# SAMD51.net
KiCad netlist of a schematic drawn in Altium Designer
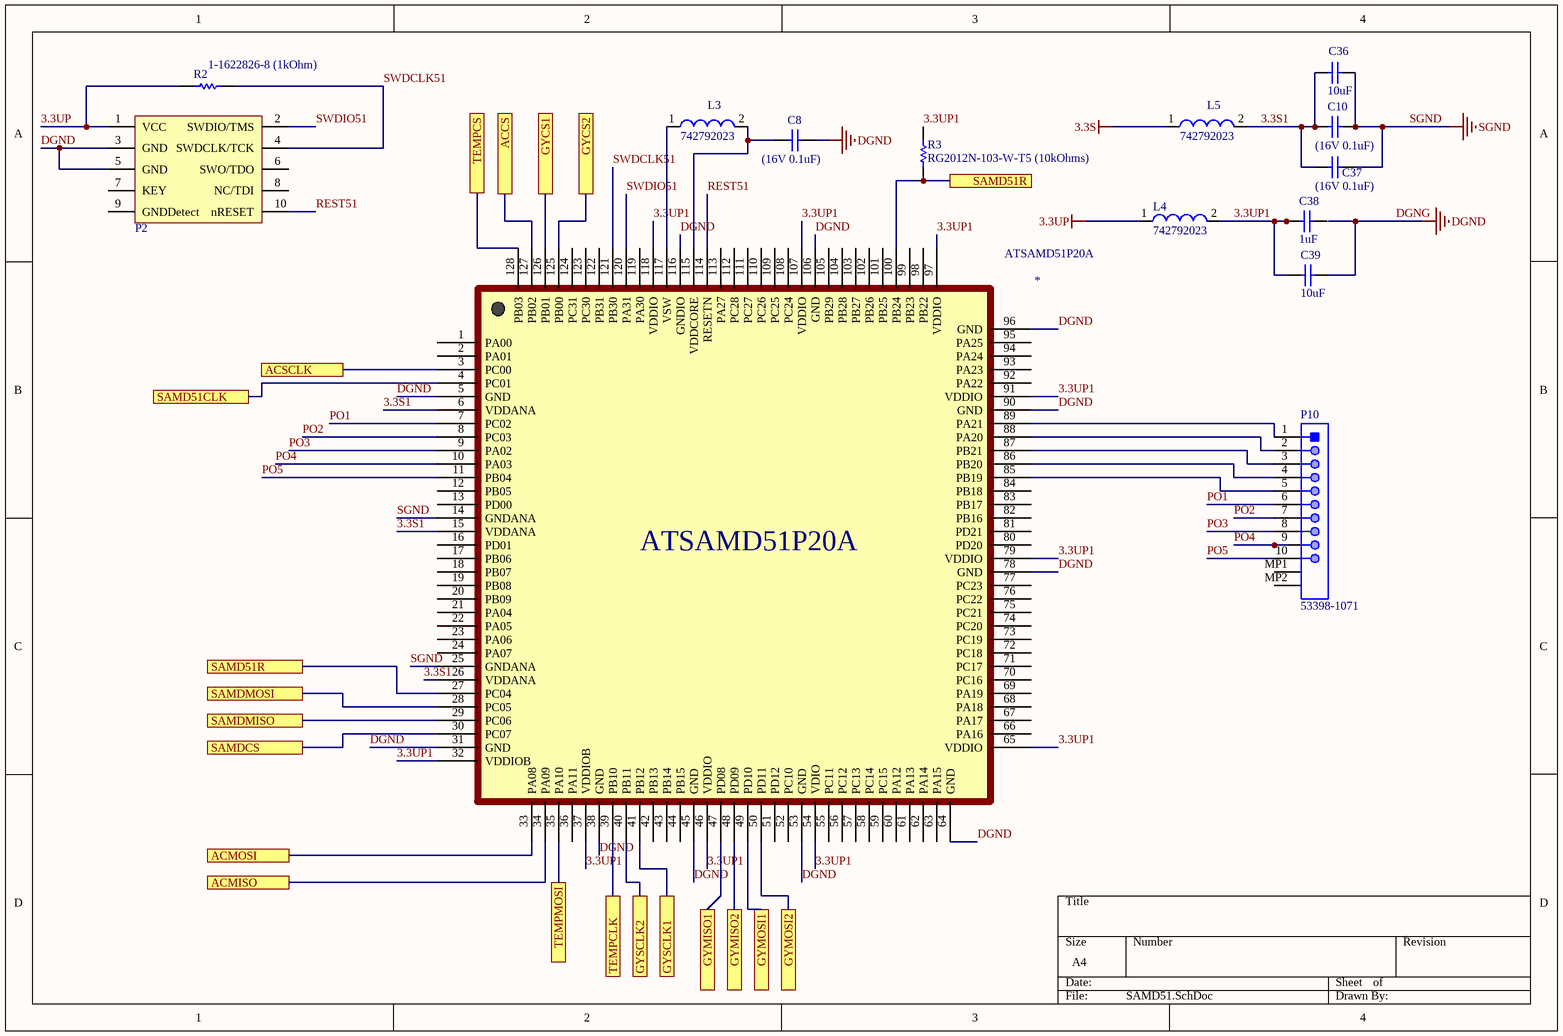
[diagram p0: SAMD51.SchDoc]

(export (version "E")
  (design (tool "Eeschema 10.0.6"))
  (components
    (comp (ref "*")
      (value "ATSAMD51P20A")
      (footprint "ATSAMD51P20A")
      (description "https://www.microchip.com/wwwproducts/en/ATSAMD51P20A#additional-features")
      (libsource (lib "ATSAMD51P20A") (part "ATSAMD51P20A"))
    )
    (comp (ref "C8")
      (value "(16V 0.1uF)")
      (footprint "CAPC1608X90X35LL15T15")
      (fields
        (field (name "PART NUMBER") "0603YC104MAT4A")
        (field (name "MANUFACTURER") "AVX Interconnect / Elco")
      )
      (libsource (lib "Altium Content Vault") (part "CAP"))
    )
    (comp (ref "C10")
      (value "(16V 0.1uF)")
      (footprint "CAPC1608X90X35LL15T15")
      (fields
        (field (name "PART NUMBER") "0603YC104MAT4A")
        (field (name "MANUFACTURER") "AVX Interconnect / Elco")
      )
      (libsource (lib "Altium Content Vault") (part "CAP"))
    )
    (comp (ref "C36")
      (value "10uF")
      (footprint "CAPC1608X90X35NL10T15")
      (fields (field (name "PART NUMBER") "GRM188R60J106ME47D") (field (name "MANUFACTURER") "Murata"))
      (libsource (lib "Altium Content Vault") (part "CAP"))
    )
    (comp (ref "C37")
      (value "(16V 0.1uF)")
      (footprint "CAPC1608X90X35LL15T15")
      (fields
        (field (name "PART NUMBER") "0603YC104MAT4A")
        (field (name "MANUFACTURER") "AVX Interconnect / Elco")
      )
      (libsource (lib "Altium Content Vault") (part "CAP"))
    )
    (comp (ref "C38")
      (value "1uF")
      (footprint "CAPC1608X90X35LL15T15")
      (fields
        (field (name "PART NUMBER") "0603ZC105KAT2A")
        (field (name "MANUFACTURER") "AVX Interconnect / Elco")
      )
      (libsource (lib "Altium Content Vault") (part "CAP"))
    )
    (comp (ref "C39")
      (value "10uF")
      (footprint "CAPC1608X90X35NL10T15")
      (fields (field (name "PART NUMBER") "GRM188R60J106ME47D") (field (name "MANUFACTURER") "Murata"))
      (libsource (lib "Altium Content Vault") (part "CAP"))
    )
    (comp (ref "L3")
      (value "742792023")
      (footprint "SMD-0805")
      (description "SMD EMI Suppression Ferrite Bead WE-CBF, Z = 120 Ohm")
      (libsource (lib "Altium Content Vault") (part "PAS-IND-INDUCTOR-2"))
    )
    (comp (ref "L4")
      (value "742792023")
      (footprint "SMD-0805")
      (description "SMD EMI Suppression Ferrite Bead WE-CBF, Z = 120 Ohm")
      (libsource (lib "Altium Content Vault") (part "PAS-IND-INDUCTOR-2"))
    )
    (comp (ref "L5")
      (value "742792023")
      (footprint "SMD-0805")
      (description "SMD EMI Suppression Ferrite Bead WE-CBF, Z = 120 Ohm")
      (libsource (lib "Altium Content Vault") (part "PAS-IND-INDUCTOR-2"))
    )
    (comp (ref "P2")
      (value "3220-10-0100-00 Pin connector for Cotex Programmers")
      (description "3220-10-0100-00 Pin connector from DigiKey")
      (libsource (lib "3220-10-0100-00") (part "3220-10-0100-00"))
    )
    (comp (ref "P10")
      (value "53398-1071")
      (footprint "MOLX-53398-1071_V")
      (description "Male Header, Pitch 1.25 mm, 1 x 10 Position, Height 4.7 mm, -40 to 85 degC, RoHS, Tape and Reel")
      (fields (field (name "MANUFACTURER") "Molex"))
      (libsource (lib "Altium Content Vault") (part "CN-1P-2M-R10"))
    )
    (comp (ref "R2")
      (value "1-1622826-8 (1kOhm)")
      (footprint "RESC1005X40X25ML10T10")
      (fields
        (field (name "MANUFACTURER") "TE Connectivity / AMP")
        (field (name "PART NUMBER") "1-1622826-8")
      )
      (libsource (lib "Altium Content Vault") (part "RES"))
    )
    (comp (ref "R3")
      (value "RG2012N-103-W-T5 (10kOhms)")
      (footprint "RESC2013X50X40NL20T20")
      (fields (field (name "MANUFACTURER") "Susumu") (field (name "PART NUMBER") "RG2012N-103-W-T5"))
      (libsource (lib "Altium Content Vault") (part "RES"))
    )
  )
  (nets
    (net (code "1") (name "/3.3S1") (class "Default")
      (node (ref "*") (pin "15") (pinfunction "VDDANA_15") (pintype "passive"))
      (node (ref "*") (pin "26") (pinfunction "VDDANA_26") (pintype "passive"))
      (node (ref "*") (pin "6") (pinfunction "VDDANA_6") (pintype "passive"))
      (node (ref "C10") (pin "1") (pinfunction "1_1") (pintype "passive"))
      (node (ref "C36") (pin "2") (pinfunction "2_2") (pintype "passive"))
      (node (ref "C37") (pin "1") (pinfunction "1_1") (pintype "passive"))
      (node (ref "L5") (pin "2") (pinfunction "2_2") (pintype "passive"))
    )
    (net (code "2") (name "/3.3UP1") (class "Default")
      (node (ref "*") (pin "107") (pinfunction "VDDIO_107") (pintype "passive"))
      (node (ref "*") (pin "118") (pinfunction "VDDIO_118") (pintype "passive"))
      (node (ref "*") (pin "32") (pinfunction "VDDIOB_32") (pintype "passive"))
      (node (ref "*") (pin "37") (pinfunction "VDDIOB_37") (pintype "passive"))
      (node (ref "*") (pin "46") (pinfunction "VDDIO_46") (pintype "passive"))
      (node (ref "*") (pin "54") (pinfunction "VDIO_54") (pintype "passive"))
      (node (ref "*") (pin "65") (pinfunction "VDDIO_65") (pintype "passive"))
      (node (ref "*") (pin "79") (pinfunction "VDDIO_79") (pintype "passive"))
      (node (ref "*") (pin "91") (pinfunction "VDDIO_91") (pintype "passive"))
      (node (ref "*") (pin "97") (pinfunction "VDDIO_97") (pintype "passive"))
      (node (ref "C38") (pin "2") (pinfunction "2_2") (pintype "passive"))
      (node (ref "C39") (pin "2") (pinfunction "2_2") (pintype "passive"))
      (node (ref "L4") (pin "2") (pinfunction "2_2") (pintype "passive"))
      (node (ref "R3") (pin "2") (pinfunction "2_2") (pintype "passive"))
    )
    (net (code "3") (name "/ACCS") (class "Default")
      (node (ref "*") (pin "127") (pinfunction "PB02_127") (pintype "passive"))
    )
    (net (code "4") (name "/ACMISO") (class "Default")
      (node (ref "*") (pin "34") (pinfunction "PA09_34") (pintype "passive"))
    )
    (net (code "5") (name "/ACMOSI") (class "Default")
      (node (ref "*") (pin "33") (pinfunction "PA08_33") (pintype "passive"))
    )
    (net (code "6") (name "/ACSCLK") (class "Default")
      (node (ref "*") (pin "3") (pinfunction "PC00_3") (pintype "passive"))
    )
    (net (code "7") (name "/GYCS1") (class "Default")
      (node (ref "*") (pin "126") (pinfunction "PB01_126") (pintype "passive"))
    )
    (net (code "8") (name "/GYCS2") (class "Default")
      (node (ref "*") (pin "125") (pinfunction "PB00_125") (pintype "passive"))
    )
    (net (code "9") (name "/GYMISO1") (class "Default")
      (node (ref "*") (pin "47") (pinfunction "PD08_47") (pintype "passive"))
    )
    (net (code "10") (name "/GYMISO2") (class "Default")
      (node (ref "*") (pin "48") (pinfunction "PD09_48") (pintype "passive"))
    )
    (net (code "11") (name "/GYMOSI1") (class "Default")
      (node (ref "*") (pin "49") (pinfunction "PD10_49") (pintype "passive"))
    )
    (net (code "12") (name "/GYMOSI2") (class "Default")
      (node (ref "*") (pin "50") (pinfunction "PD11_50") (pintype "passive"))
    )
    (net (code "13") (name "/GYSCLK1") (class "Default")
      (node (ref "*") (pin "41") (pinfunction "PB12_41") (pintype "passive"))
    )
    (net (code "14") (name "/GYSCLK2") (class "Default")
      (node (ref "*") (pin "40") (pinfunction "PB11_40") (pintype "passive"))
    )
    (net (code "15") (name "/PO1") (class "Default")
      (node (ref "*") (pin "7") (pinfunction "PC02_7") (pintype "passive"))
      (node (ref "P10") (pin "6") (pinfunction "6_6") (pintype "passive"))
    )
    (net (code "16") (name "/PO2") (class "Default")
      (node (ref "*") (pin "8") (pinfunction "PC03_8") (pintype "passive"))
      (node (ref "P10") (pin "7") (pinfunction "7_7") (pintype "passive"))
    )
    (net (code "17") (name "/PO3") (class "Default")
      (node (ref "*") (pin "9") (pinfunction "PA02_9") (pintype "passive"))
      (node (ref "P10") (pin "8") (pinfunction "8_8") (pintype "passive"))
    )
    (net (code "18") (name "/PO4") (class "Default")
      (node (ref "*") (pin "10") (pinfunction "PA03_10") (pintype "passive"))
      (node (ref "P10") (pin "9") (pinfunction "9_9") (pintype "passive"))
    )
    (net (code "19") (name "/PO5") (class "Default")
      (node (ref "*") (pin "11") (pinfunction "PB04_11") (pintype "passive"))
      (node (ref "P10") (pin "10") (pinfunction "10_10") (pintype "passive"))
    )
    (net (code "20") (name "/REST51") (class "Default")
      (node (ref "*") (pin "114") (pinfunction "RESETN_114") (pintype "passive"))
      (node (ref "P2") (pin "10") (pinfunction "nRESET_10") (pintype "passive"))
    )
    (net (code "21") (name "/SAMD51CLK") (class "Default")
      (node (ref "*") (pin "4") (pinfunction "PC01_4") (pintype "passive"))
    )
    (net (code "22") (name "/SAMD51R") (class "Default")
      (node (ref "*") (pin "100") (pinfunction "PB24_100") (pintype "passive"))
      (node (ref "*") (pin "27") (pinfunction "PC04_27") (pintype "passive"))
      (node (ref "R3") (pin "1") (pinfunction "1_1") (pintype "passive"))
    )
    (net (code "23") (name "/SAMDCS") (class "Default")
      (node (ref "*") (pin "30") (pinfunction "PC07_30") (pintype "passive"))
    )
    (net (code "24") (name "/SAMDMISO") (class "Default")
      (node (ref "*") (pin "29") (pinfunction "PC06_29") (pintype "passive"))
    )
    (net (code "25") (name "/SAMDMOSI") (class "Default")
      (node (ref "*") (pin "28") (pinfunction "PC05_28") (pintype "passive"))
    )
    (net (code "26") (name "/SWDCLK51") (class "Default")
      (node (ref "*") (pin "121") (pinfunction "PB30_121") (pintype "passive"))
      (node (ref "P2") (pin "4") (pinfunction "SWDCLK/TCK_4") (pintype "passive"))
      (node (ref "R2") (pin "1") (pinfunction "1_1") (pintype "passive"))
    )
    (net (code "27") (name "/SWDIO51") (class "Default")
      (node (ref "*") (pin "120") (pinfunction "PA31_120") (pintype "passive"))
      (node (ref "P2") (pin "2") (pinfunction "SWDIO/TMS_2") (pintype "passive"))
    )
    (net (code "28") (name "/TEMPCLK") (class "Default")
      (node (ref "*") (pin "39") (pinfunction "PB10_39") (pintype "passive"))
    )
    (net (code "29") (name "/TEMPCS") (class "Default")
      (node (ref "*") (pin "128") (pinfunction "PB03_128") (pintype "passive"))
    )
    (net (code "30") (name "/TEMPMOSI") (class "Default")
      (node (ref "*") (pin "35") (pinfunction "PA10_35") (pintype "passive"))
    )
    (net (code "31") (name "3.3S") (class "Default")
      (node (ref "L5") (pin "1") (pinfunction "1_1") (pintype "passive"))
    )
    (net (code "32") (name "3.3UP") (class "Default")
      (node (ref "L4") (pin "1") (pinfunction "1_1") (pintype "passive"))
      (node (ref "P2") (pin "1") (pinfunction "VCC_1") (pintype "passive"))
      (node (ref "R2") (pin "2") (pinfunction "2_2") (pintype "passive"))
    )
    (net (code "33") (name "DGND") (class "Default")
      (node (ref "*") (pin "106") (pinfunction "GND_106") (pintype "passive"))
      (node (ref "*") (pin "116") (pinfunction "GNDIO_116") (pintype "passive"))
      (node (ref "*") (pin "31") (pinfunction "GND_31") (pintype "passive"))
      (node (ref "*") (pin "38") (pinfunction "GND_38") (pintype "passive"))
      (node (ref "*") (pin "45") (pinfunction "GND_45") (pintype "passive"))
      (node (ref "*") (pin "5") (pinfunction "GND_5") (pintype "passive"))
      (node (ref "*") (pin "53") (pinfunction "GND_53") (pintype "passive"))
      (node (ref "*") (pin "64") (pinfunction "GND_64") (pintype "passive"))
      (node (ref "*") (pin "78") (pinfunction "GND_78") (pintype "passive"))
      (node (ref "*") (pin "90") (pinfunction "GND_90") (pintype "passive"))
      (node (ref "*") (pin "96") (pinfunction "GND_96") (pintype "passive"))
      (node (ref "C39") (pin "1") (pinfunction "1_1") (pintype "passive"))
      (node (ref "C8") (pin "2") (pinfunction "2_2") (pintype "passive"))
      (node (ref "P2") (pin "3") (pinfunction "GND_3") (pintype "passive"))
      (node (ref "P2") (pin "5") (pinfunction "GND_5") (pintype "passive"))
    )
    (net (code "34") (name "Net-(*-PA20)") (class "Default")
      (node (ref "*") (pin "88") (pinfunction "PA20_88") (pintype "passive"))
      (node (ref "P10") (pin "2") (pinfunction "2_2") (pintype "passive"))
    )
    (net (code "35") (name "Net-(*-PA21)") (class "Default")
      (node (ref "*") (pin "89") (pinfunction "PA21_89") (pintype "passive"))
      (node (ref "P10") (pin "1") (pinfunction "1_1") (pintype "passive"))
    )
    (net (code "36") (name "Net-(*-PB19)") (class "Default")
      (node (ref "*") (pin "85") (pinfunction "PB19_85") (pintype "passive"))
      (node (ref "P10") (pin "5") (pinfunction "5_5") (pintype "passive"))
    )
    (net (code "37") (name "Net-(*-PB20)") (class "Default")
      (node (ref "*") (pin "86") (pinfunction "PB20_86") (pintype "passive"))
      (node (ref "P10") (pin "4") (pinfunction "4_4") (pintype "passive"))
    )
    (net (code "38") (name "Net-(*-PB21)") (class "Default")
      (node (ref "*") (pin "87") (pinfunction "PB21_87") (pintype "passive"))
      (node (ref "P10") (pin "3") (pinfunction "3_3") (pintype "passive"))
    )
    (net (code "39") (name "Net-(*-VDDCORE)") (class "Default")
      (node (ref "*") (pin "115") (pinfunction "VDDCORE_115") (pintype "passive"))
      (node (ref "C8") (pin "1") (pinfunction "1_1") (pintype "passive"))
      (node (ref "L3") (pin "2") (pinfunction "2_2") (pintype "passive"))
    )
    (net (code "40") (name "Net-(*-VSW)") (class "Default")
      (node (ref "*") (pin "117") (pinfunction "VSW_117") (pintype "passive"))
      (node (ref "L3") (pin "1") (pinfunction "1_1") (pintype "passive"))
    )
    (net (code "41") (name "SGND") (class "Default")
      (node (ref "*") (pin "14") (pinfunction "GNDANA_14") (pintype "passive"))
      (node (ref "*") (pin "25") (pinfunction "GNDANA_25") (pintype "passive"))
      (node (ref "C10") (pin "2") (pinfunction "2_2") (pintype "passive"))
      (node (ref "C36") (pin "1") (pinfunction "1_1") (pintype "passive"))
      (node (ref "C37") (pin "2") (pinfunction "2_2") (pintype "passive"))
    )
    (net (code "42") (name "unconnected-(*-PA00-Pad1)") (class "Default")
      (node (ref "*") (pin "1") (pinfunction "PA00_1") (pintype "passive"))
    )
    (net (code "43") (name "unconnected-(*-PA01-Pad2)") (class "Default")
      (node (ref "*") (pin "2") (pinfunction "PA01_2") (pintype "passive"))
    )
    (net (code "44") (name "unconnected-(*-PA04-Pad21)") (class "Default")
      (node (ref "*") (pin "21") (pinfunction "PA04_21") (pintype "passive"))
    )
    (net (code "45") (name "unconnected-(*-PA05-Pad22)") (class "Default")
      (node (ref "*") (pin "22") (pinfunction "PA05_22") (pintype "passive"))
    )
    (net (code "46") (name "unconnected-(*-PA06-Pad23)") (class "Default")
      (node (ref "*") (pin "23") (pinfunction "PA06_23") (pintype "passive"))
    )
    (net (code "47") (name "unconnected-(*-PA07-Pad24)") (class "Default")
      (node (ref "*") (pin "24") (pinfunction "PA07_24") (pintype "passive"))
    )
    (net (code "48") (name "unconnected-(*-PA11-Pad36)") (class "Default")
      (node (ref "*") (pin "36") (pinfunction "PA11_36") (pintype "passive"))
    )
    (net (code "49") (name "unconnected-(*-PA12-Pad60)") (class "Default")
      (node (ref "*") (pin "60") (pinfunction "PA12_60") (pintype "passive"))
    )
    (net (code "50") (name "unconnected-(*-PA13-Pad61)") (class "Default")
      (node (ref "*") (pin "61") (pinfunction "PA13_61") (pintype "passive"))
    )
    (net (code "51") (name "unconnected-(*-PA14-Pad62)") (class "Default")
      (node (ref "*") (pin "62") (pinfunction "PA14_62") (pintype "passive"))
    )
    (net (code "52") (name "unconnected-(*-PA15-Pad63)") (class "Default")
      (node (ref "*") (pin "63") (pinfunction "PA15_63") (pintype "passive"))
    )
    (net (code "53") (name "unconnected-(*-PA16-Pad66)") (class "Default")
      (node (ref "*") (pin "66") (pinfunction "PA16_66") (pintype "passive"))
    )
    (net (code "54") (name "unconnected-(*-PA17-Pad67)") (class "Default")
      (node (ref "*") (pin "67") (pinfunction "PA17_67") (pintype "passive"))
    )
    (net (code "55") (name "unconnected-(*-PA18-Pad68)") (class "Default")
      (node (ref "*") (pin "68") (pinfunction "PA18_68") (pintype "passive"))
    )
    (net (code "56") (name "unconnected-(*-PA19-Pad69)") (class "Default")
      (node (ref "*") (pin "69") (pinfunction "PA19_69") (pintype "passive"))
    )
    (net (code "57") (name "unconnected-(*-PA22-Pad92)") (class "Default")
      (node (ref "*") (pin "92") (pinfunction "PA22_92") (pintype "passive"))
    )
    (net (code "58") (name "unconnected-(*-PA23-Pad93)") (class "Default")
      (node (ref "*") (pin "93") (pinfunction "PA23_93") (pintype "passive"))
    )
    (net (code "59") (name "unconnected-(*-PA24-Pad94)") (class "Default")
      (node (ref "*") (pin "94") (pinfunction "PA24_94") (pintype "passive"))
    )
    (net (code "60") (name "unconnected-(*-PA25-Pad95)") (class "Default")
      (node (ref "*") (pin "95") (pinfunction "PA25_95") (pintype "passive"))
    )
    (net (code "61") (name "unconnected-(*-PA27-Pad113)") (class "Default")
      (node (ref "*") (pin "113") (pinfunction "PA27_113") (pintype "passive"))
    )
    (net (code "62") (name "unconnected-(*-PA30-Pad119)") (class "Default")
      (node (ref "*") (pin "119") (pinfunction "PA30_119") (pintype "passive"))
    )
    (net (code "63") (name "unconnected-(*-PB05-Pad12)") (class "Default")
      (node (ref "*") (pin "12") (pinfunction "PB05_12") (pintype "passive"))
    )
    (net (code "64") (name "unconnected-(*-PB06-Pad17)") (class "Default")
      (node (ref "*") (pin "17") (pinfunction "PB06_17") (pintype "passive"))
    )
    (net (code "65") (name "unconnected-(*-PB07-Pad18)") (class "Default")
      (node (ref "*") (pin "18") (pinfunction "PB07_18") (pintype "passive"))
    )
    (net (code "66") (name "unconnected-(*-PB08-Pad19)") (class "Default")
      (node (ref "*") (pin "19") (pinfunction "PB08_19") (pintype "passive"))
    )
    (net (code "67") (name "unconnected-(*-PB09-Pad20)") (class "Default")
      (node (ref "*") (pin "20") (pinfunction "PB09_20") (pintype "passive"))
    )
    (net (code "68") (name "unconnected-(*-PB13-Pad42)") (class "Default")
      (node (ref "*") (pin "42") (pinfunction "PB13_42") (pintype "passive"))
    )
    (net (code "69") (name "unconnected-(*-PB14-Pad43)") (class "Default")
      (node (ref "*") (pin "43") (pinfunction "PB14_43") (pintype "passive"))
    )
    (net (code "70") (name "unconnected-(*-PB15-Pad44)") (class "Default")
      (node (ref "*") (pin "44") (pinfunction "PB15_44") (pintype "passive"))
    )
    (net (code "71") (name "unconnected-(*-PB16-Pad82)") (class "Default")
      (node (ref "*") (pin "82") (pinfunction "PB16_82") (pintype "passive"))
    )
    (net (code "72") (name "unconnected-(*-PB17-Pad83)") (class "Default")
      (node (ref "*") (pin "83") (pinfunction "PB17_83") (pintype "passive"))
    )
    (net (code "73") (name "unconnected-(*-PB18-Pad84)") (class "Default")
      (node (ref "*") (pin "84") (pinfunction "PB18_84") (pintype "passive"))
    )
    (net (code "74") (name "unconnected-(*-PB22-Pad98)") (class "Default")
      (node (ref "*") (pin "98") (pinfunction "PB22_98") (pintype "passive"))
    )
    (net (code "75") (name "unconnected-(*-PB23-Pad99)") (class "Default")
      (node (ref "*") (pin "99") (pinfunction "PB23_99") (pintype "passive"))
    )
    (net (code "76") (name "unconnected-(*-PB25-Pad101)") (class "Default")
      (node (ref "*") (pin "101") (pinfunction "PB25_101") (pintype "passive"))
    )
    (net (code "77") (name "unconnected-(*-PB26-Pad102)") (class "Default")
      (node (ref "*") (pin "102") (pinfunction "PB26_102") (pintype "passive"))
    )
    (net (code "78") (name "unconnected-(*-PB27-Pad103)") (class "Default")
      (node (ref "*") (pin "103") (pinfunction "PB27_103") (pintype "passive"))
    )
    (net (code "79") (name "unconnected-(*-PB28-Pad104)") (class "Default")
      (node (ref "*") (pin "104") (pinfunction "PB28_104") (pintype "passive"))
    )
    (net (code "80") (name "unconnected-(*-PB29-Pad105)") (class "Default")
      (node (ref "*") (pin "105") (pinfunction "PB29_105") (pintype "passive"))
    )
    (net (code "81") (name "unconnected-(*-PB31-Pad122)") (class "Default")
      (node (ref "*") (pin "122") (pinfunction "PB31_122") (pintype "passive"))
    )
    (net (code "82") (name "unconnected-(*-PC10-Pad52)") (class "Default")
      (node (ref "*") (pin "52") (pinfunction "PC10_52") (pintype "passive"))
    )
    (net (code "83") (name "unconnected-(*-PC11-Pad55)") (class "Default")
      (node (ref "*") (pin "55") (pinfunction "PC11_55") (pintype "passive"))
    )
    (net (code "84") (name "unconnected-(*-PC12-Pad56)") (class "Default")
      (node (ref "*") (pin "56") (pinfunction "PC12_56") (pintype "passive"))
    )
    (net (code "85") (name "unconnected-(*-PC13-Pad57)") (class "Default")
      (node (ref "*") (pin "57") (pinfunction "PC13_57") (pintype "passive"))
    )
    (net (code "86") (name "unconnected-(*-PC14-Pad58)") (class "Default")
      (node (ref "*") (pin "58") (pinfunction "PC14_58") (pintype "passive"))
    )
    (net (code "87") (name "unconnected-(*-PC15-Pad59)") (class "Default")
      (node (ref "*") (pin "59") (pinfunction "PC15_59") (pintype "passive"))
    )
    (net (code "88") (name "unconnected-(*-PC16-Pad70)") (class "Default")
      (node (ref "*") (pin "70") (pinfunction "PC16_70") (pintype "passive"))
    )
    (net (code "89") (name "unconnected-(*-PC17-Pad71)") (class "Default")
      (node (ref "*") (pin "71") (pinfunction "PC17_71") (pintype "passive"))
    )
    (net (code "90") (name "unconnected-(*-PC18-Pad72)") (class "Default")
      (node (ref "*") (pin "72") (pinfunction "PC18_72") (pintype "passive"))
    )
    (net (code "91") (name "unconnected-(*-PC19-Pad73)") (class "Default")
      (node (ref "*") (pin "73") (pinfunction "PC19_73") (pintype "passive"))
    )
    (net (code "92") (name "unconnected-(*-PC20-Pad74)") (class "Default")
      (node (ref "*") (pin "74") (pinfunction "PC20_74") (pintype "passive"))
    )
    (net (code "93") (name "unconnected-(*-PC21-Pad75)") (class "Default")
      (node (ref "*") (pin "75") (pinfunction "PC21_75") (pintype "passive"))
    )
    (net (code "94") (name "unconnected-(*-PC22-Pad76)") (class "Default")
      (node (ref "*") (pin "76") (pinfunction "PC22_76") (pintype "passive"))
    )
    (net (code "95") (name "unconnected-(*-PC23-Pad77)") (class "Default")
      (node (ref "*") (pin "77") (pinfunction "PC23_77") (pintype "passive"))
    )
    (net (code "96") (name "unconnected-(*-PC24-Pad108)") (class "Default")
      (node (ref "*") (pin "108") (pinfunction "PC24_108") (pintype "passive"))
    )
    (net (code "97") (name "unconnected-(*-PC25-Pad109)") (class "Default")
      (node (ref "*") (pin "109") (pinfunction "PC25_109") (pintype "passive"))
    )
    (net (code "98") (name "unconnected-(*-PC26-Pad110)") (class "Default")
      (node (ref "*") (pin "110") (pinfunction "PC26_110") (pintype "passive"))
    )
    (net (code "99") (name "unconnected-(*-PC27-Pad111)") (class "Default")
      (node (ref "*") (pin "111") (pinfunction "PC27_111") (pintype "passive"))
    )
    (net (code "100") (name "unconnected-(*-PC28-Pad112)") (class "Default")
      (node (ref "*") (pin "112") (pinfunction "PC28_112") (pintype "passive"))
    )
    (net (code "101") (name "unconnected-(*-PC30-Pad123)") (class "Default")
      (node (ref "*") (pin "123") (pinfunction "PC30_123") (pintype "passive"))
    )
    (net (code "102") (name "unconnected-(*-PC31-Pad124)") (class "Default")
      (node (ref "*") (pin "124") (pinfunction "PC31_124") (pintype "passive"))
    )
    (net (code "103") (name "unconnected-(*-PD00-Pad13)") (class "Default")
      (node (ref "*") (pin "13") (pinfunction "PD00_13") (pintype "passive"))
    )
    (net (code "104") (name "unconnected-(*-PD01-Pad16)") (class "Default")
      (node (ref "*") (pin "16") (pinfunction "PD01_16") (pintype "passive"))
    )
    (net (code "105") (name "unconnected-(*-PD12-Pad51)") (class "Default")
      (node (ref "*") (pin "51") (pinfunction "PD12_51") (pintype "passive"))
    )
    (net (code "106") (name "unconnected-(*-PD20-Pad80)") (class "Default")
      (node (ref "*") (pin "80") (pinfunction "PD20_80") (pintype "passive"))
    )
    (net (code "107") (name "unconnected-(*-PD21-Pad81)") (class "Default")
      (node (ref "*") (pin "81") (pinfunction "PD21_81") (pintype "passive"))
    )
    (net (code "108") (name "unconnected-(C38-Pad1)") (class "Default")
      (node (ref "C38") (pin "1") (pinfunction "1_1") (pintype "passive"))
    )
    (net (code "109") (name "unconnected-(P2-GNDDetect-Pad9)") (class "Default")
      (node (ref "P2") (pin "9") (pinfunction "GNDDetect_9") (pintype "passive"))
    )
    (net (code "110") (name "unconnected-(P2-KEY-Pad7)") (class "Default")
      (node (ref "P2") (pin "7") (pinfunction "KEY_7") (pintype "passive"))
    )
    (net (code "111") (name "unconnected-(P2-NC{slash}TDI-Pad8)") (class "Default")
      (node (ref "P2") (pin "8") (pinfunction "NC/TDI_8") (pintype "passive"))
    )
    (net (code "112") (name "unconnected-(P2-SWO{slash}TDO-Pad6)") (class "Default")
      (node (ref "P2") (pin "6") (pinfunction "SWO/TDO_6") (pintype "passive"))
    )
    (net (code "113") (name "unconnected-(P10-PadMP1)") (class "Default")
      (node (ref "P10") (pin "MP1") (pinfunction "MP1_MP1") (pintype "passive"))
    )
    (net (code "114") (name "unconnected-(P10-PadMP2)") (class "Default")
      (node (ref "P10") (pin "MP2") (pinfunction "MP2_MP2") (pintype "passive"))
    )
  )
)
